# emat_igbt_switch.net
KiCad netlist of a schematic drawn in EAGLE
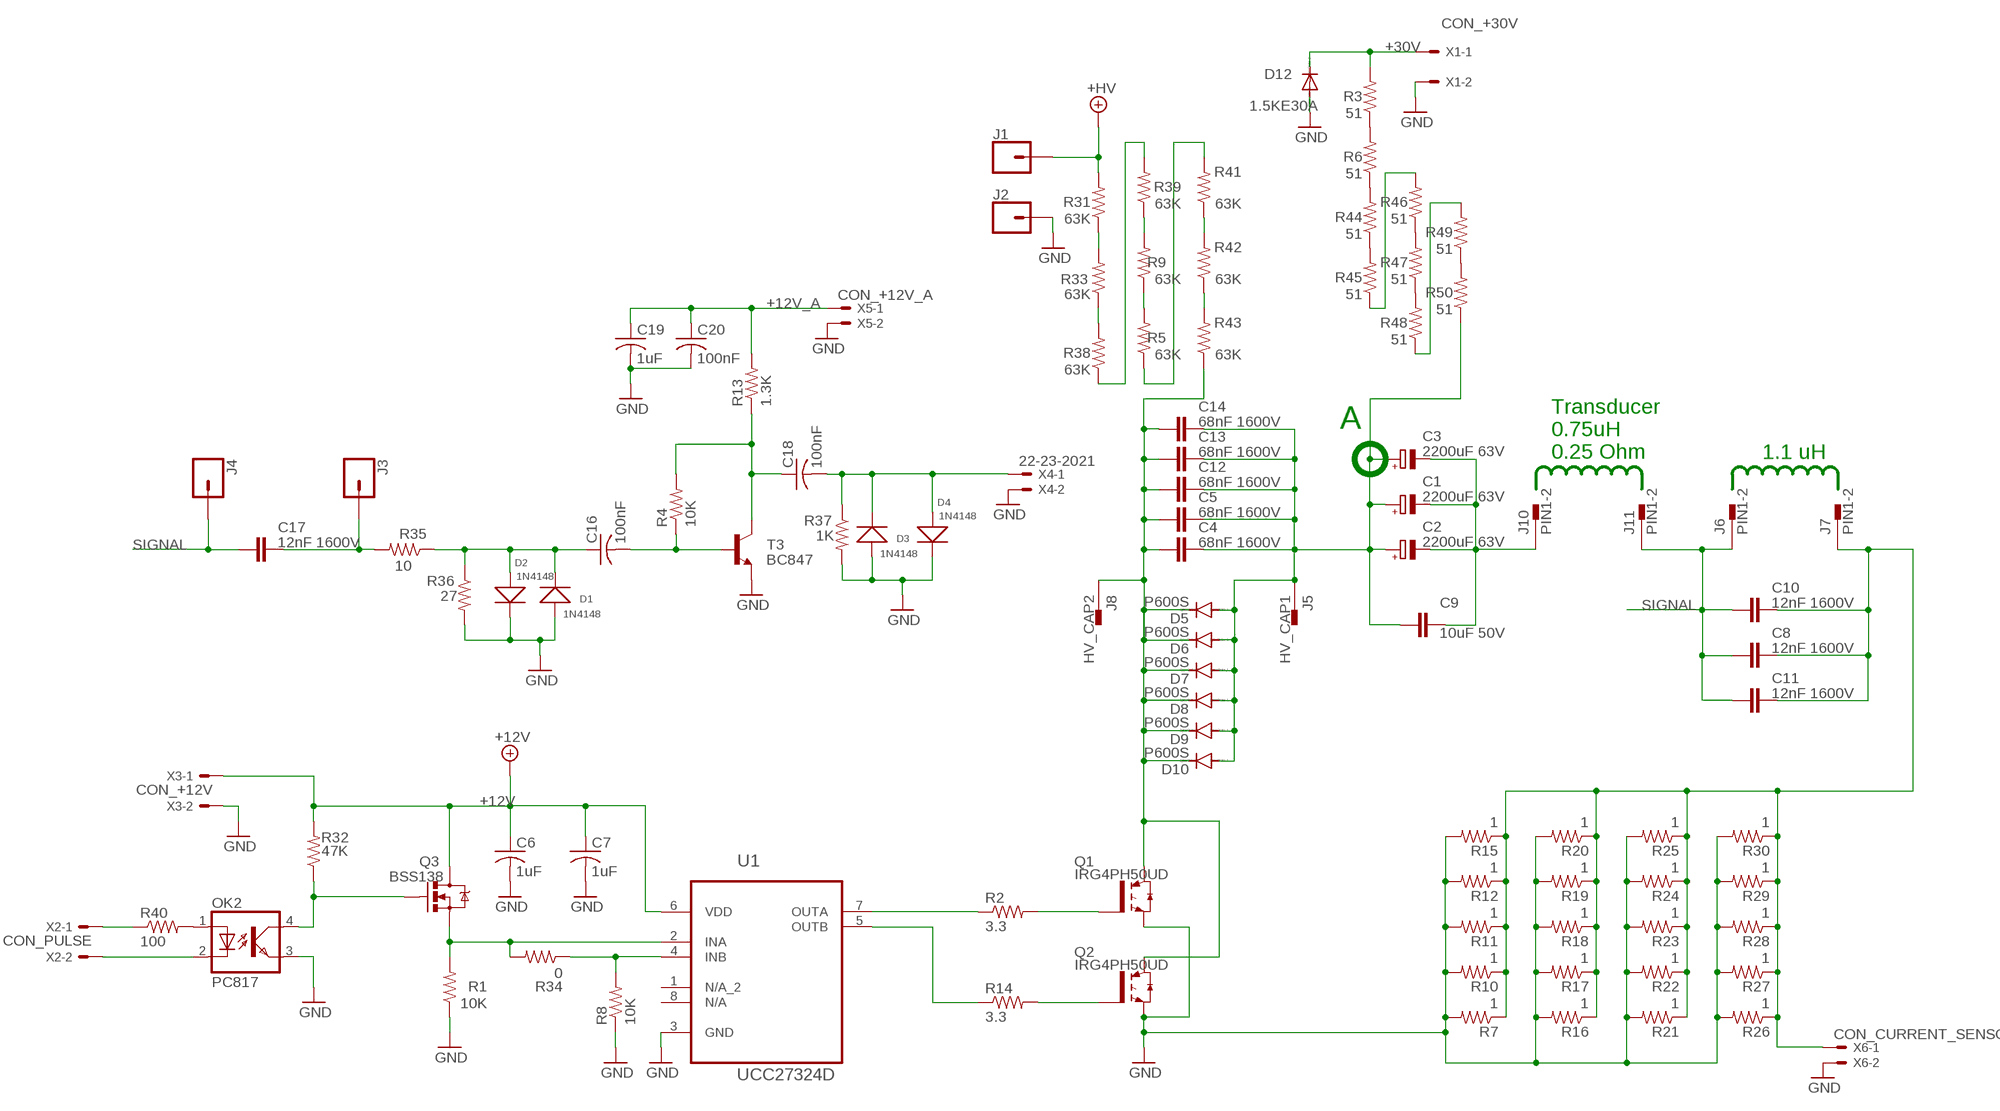
[diagram p0: schematic, sheet 1]

(export (version "E")
  (design (tool "Eeschema 10.0.6"))
  (components
    (comp (ref "C1")
      (value "2200uF 63V")
      (footprint "eagle-import:E7,5-18")
      (libsource (lib "eagle-import") (part "CPOL-EUE7.5-18"))
    )
    (comp (ref "C2")
      (value "2200uF 63V")
      (footprint "eagle-import:E7,5-18")
      (libsource (lib "eagle-import") (part "CPOL-EUE7.5-18"))
    )
    (comp (ref "C3")
      (value "2200uF 63V")
      (footprint "eagle-import:E7,5-18")
      (libsource (lib "eagle-import") (part "CPOL-EUE7.5-18"))
    )
    (comp (ref "C4")
      (value "68nF 1600V")
      (footprint "eagle-import:C37.5B15")
      (libsource (lib "eagle-import") (part "C37/15"))
    )
    (comp (ref "C5")
      (value "68nF 1600V")
      (footprint "eagle-import:C37.5B15")
      (libsource (lib "eagle-import") (part "C37/15"))
    )
    (comp (ref "C6")
      (value "1uF")
      (footprint "eagle-import:C0805")
      (libsource (lib "eagle-import") (part "C-USC0805"))
    )
    (comp (ref "C7")
      (value "1uF")
      (footprint "eagle-import:C0805")
      (libsource (lib "eagle-import") (part "C-USC0805"))
    )
    (comp (ref "C8")
      (value "12nF 1600V")
      (footprint "eagle-import:C22.5B10")
      (libsource (lib "eagle-import") (part "C22/10"))
    )
    (comp (ref "C9")
      (value "10uF 50V")
      (footprint "eagle-import:C2220K")
      (libsource (lib "eagle-import") (part "C-EUC2220K"))
    )
    (comp (ref "C10")
      (value "12nF 1600V")
      (footprint "eagle-import:C22.5B10")
      (libsource (lib "eagle-import") (part "C22/10"))
    )
    (comp (ref "C11")
      (value "12nF 1600V")
      (footprint "eagle-import:C22.5B10")
      (libsource (lib "eagle-import") (part "C22/10"))
    )
    (comp (ref "C12")
      (value "68nF 1600V")
      (footprint "eagle-import:C37.5B15")
      (libsource (lib "eagle-import") (part "C37/15"))
    )
    (comp (ref "C13")
      (value "68nF 1600V")
      (footprint "eagle-import:C37.5B15")
      (libsource (lib "eagle-import") (part "C37/15"))
    )
    (comp (ref "C14")
      (value "68nF 1600V")
      (footprint "eagle-import:C37.5B15")
      (libsource (lib "eagle-import") (part "C37/15"))
    )
    (comp (ref "C16")
      (value "100nF")
      (footprint "eagle-import:C0805")
      (libsource (lib "eagle-import") (part "C-USC0805"))
    )
    (comp (ref "C17")
      (value "12nF 1600V")
      (footprint "eagle-import:C22.5B10")
      (libsource (lib "eagle-import") (part "C22/10"))
    )
    (comp (ref "C18")
      (value "100nF")
      (footprint "eagle-import:C0805")
      (libsource (lib "eagle-import") (part "C-USC0805"))
    )
    (comp (ref "C19")
      (value "1uF")
      (footprint "eagle-import:C0805")
      (libsource (lib "eagle-import") (part "C-USC0805"))
    )
    (comp (ref "C20")
      (value "100nF")
      (footprint "eagle-import:C0805")
      (libsource (lib "eagle-import") (part "C-USC0805"))
    )
    (comp (ref "D1")
      (value "1N4148")
      (footprint "eagle-import:LL-34")
      (libsource (lib "eagle-import") (part "SMD-DIODE-SWITCH-1N4148(LL-34)"))
    )
    (comp (ref "D2")
      (value "1N4148")
      (footprint "eagle-import:LL-34")
      (libsource (lib "eagle-import") (part "SMD-DIODE-SWITCH-1N4148(LL-34)"))
    )
    (comp (ref "D3")
      (value "1N4148")
      (footprint "eagle-import:LL-34")
      (libsource (lib "eagle-import") (part "SMD-DIODE-SWITCH-1N4148(LL-34)"))
    )
    (comp (ref "D4")
      (value "1N4148")
      (footprint "eagle-import:LL-34")
      (libsource (lib "eagle-import") (part "SMD-DIODE-SWITCH-1N4148(LL-34)"))
    )
    (comp (ref "D5")
      (value "P600S")
      (footprint "eagle-import:P6-15")
      (libsource (lib "eagle-import") (part "P600"))
    )
    (comp (ref "D6")
      (value "P600S")
      (footprint "eagle-import:P6-15")
      (libsource (lib "eagle-import") (part "P600"))
    )
    (comp (ref "D7")
      (value "P600S")
      (footprint "eagle-import:P6-15")
      (libsource (lib "eagle-import") (part "P600"))
    )
    (comp (ref "D8")
      (value "P600S")
      (footprint "eagle-import:P6-15")
      (libsource (lib "eagle-import") (part "P600"))
    )
    (comp (ref "D9")
      (value "P600S")
      (footprint "eagle-import:P6-15")
      (libsource (lib "eagle-import") (part "P600"))
    )
    (comp (ref "D10")
      (value "P600S")
      (footprint "eagle-import:P6-15")
      (libsource (lib "eagle-import") (part "P600"))
    )
    (comp (ref "D12")
      (value "1.5KE30A")
      (footprint "eagle-import:SMC")
      (libsource (lib "eagle-import") (part "DIODE-SMC"))
    )
    (comp (ref "J1")
      (value "CONN_01PTH_NO_SILK_KIT")
      (footprint "eagle-import:1X01NS_KIT")
      (libsource (lib "eagle-import") (part "CONN_01PTH_NO_SILK_KIT"))
    )
    (comp (ref "J2")
      (value "CONN_01PTH_NO_SILK_KIT")
      (footprint "eagle-import:1X01NS_KIT")
      (libsource (lib "eagle-import") (part "CONN_01PTH_NO_SILK_KIT"))
    )
    (comp (ref "J3")
      (value "CONN_01PTH_NO_SILK_KIT")
      (footprint "eagle-import:1X01NS_KIT")
      (libsource (lib "eagle-import") (part "CONN_01PTH_NO_SILK_KIT"))
    )
    (comp (ref "J4")
      (value "CONN_01PTH_NO_SILK_KIT")
      (footprint "eagle-import:1X01NS_KIT")
      (libsource (lib "eagle-import") (part "CONN_01PTH_NO_SILK_KIT"))
    )
    (comp (ref "J5")
      (value "HV_CAP1")
      (footprint "eagle-import:62221")
      (fields (field (name "MF") "TYCO ELECTRONICS") (field (name "MPN") "62221-1"))
      (libsource (lib "eagle-import") (part "PIN1-2"))
    )
    (comp (ref "J6")
      (value "PIN1-2")
      (footprint "eagle-import:62221")
      (fields (field (name "MF") "TYCO ELECTRONICS") (field (name "MPN") "62221-1"))
      (libsource (lib "eagle-import") (part "PIN1-2"))
    )
    (comp (ref "J7")
      (value "PIN1-2")
      (footprint "eagle-import:62221")
      (fields (field (name "MF") "TYCO ELECTRONICS") (field (name "MPN") "62221-1"))
      (libsource (lib "eagle-import") (part "PIN1-2"))
    )
    (comp (ref "J8")
      (value "HV_CAP2")
      (footprint "eagle-import:62221")
      (fields (field (name "MF") "TYCO ELECTRONICS") (field (name "MPN") "62221-1"))
      (libsource (lib "eagle-import") (part "PIN1-2"))
    )
    (comp (ref "J10")
      (value "PIN1-2")
      (footprint "eagle-import:62221")
      (fields (field (name "MF") "TYCO ELECTRONICS") (field (name "MPN") "62221-1"))
      (libsource (lib "eagle-import") (part "PIN1-2"))
    )
    (comp (ref "J11")
      (value "PIN1-2")
      (footprint "eagle-import:62221")
      (fields (field (name "MF") "TYCO ELECTRONICS") (field (name "MPN") "62221-1"))
      (libsource (lib "eagle-import") (part "PIN1-2"))
    )
    (comp (ref "OK2")
      (value "PC817")
      (footprint "eagle-import:DIL04")
      (fields (field (name "MPN") "PC817X4J000F"))
      (libsource (lib "eagle-import") (part "PC817"))
    )
    (comp (ref "Q1")
      (value "IRG4PH50UD")
      (footprint "eagle-import:TO247BV")
      (libsource (lib "eagle-import") (part "IGBT_TO247"))
    )
    (comp (ref "Q2")
      (value "IRG4PH50UD")
      (footprint "eagle-import:TO247BV")
      (libsource (lib "eagle-import") (part "IGBT_TO247"))
    )
    (comp (ref "Q3")
      (value "BSS138")
      (footprint "eagle-import:SOT23-3")
      (libsource (lib "eagle-import") (part "MOSFET-NCHANNELBSS138"))
    )
    (comp (ref "R1")
      (value "10K")
      (footprint "eagle-import:R1206")
      (libsource (lib "eagle-import") (part "R-US_R1206"))
    )
    (comp (ref "R2")
      (value "3.3")
      (footprint "eagle-import:R1206")
      (libsource (lib "eagle-import") (part "R-US_R1206"))
    )
    (comp (ref "R3")
      (value "51")
      (footprint "eagle-import:R1206")
      (libsource (lib "eagle-import") (part "R-US_R1206"))
    )
    (comp (ref "R4")
      (value "10K")
      (footprint "eagle-import:R1206")
      (libsource (lib "eagle-import") (part "R-US_R1206"))
    )
    (comp (ref "R5")
      (value "63K")
      (footprint "eagle-import:R1206")
      (libsource (lib "eagle-import") (part "R-US_R1206"))
    )
    (comp (ref "R6")
      (value "51")
      (footprint "eagle-import:R1206")
      (libsource (lib "eagle-import") (part "R-US_R1206"))
    )
    (comp (ref "R7")
      (value "1")
      (footprint "eagle-import:R1206")
      (libsource (lib "eagle-import") (part "R-US_R1206"))
    )
    (comp (ref "R8")
      (value "10K")
      (footprint "eagle-import:R1206")
      (libsource (lib "eagle-import") (part "R-US_R1206"))
    )
    (comp (ref "R9")
      (value "63K")
      (footprint "eagle-import:R1206")
      (libsource (lib "eagle-import") (part "R-US_R1206"))
    )
    (comp (ref "R10")
      (value "1")
      (footprint "eagle-import:R1206")
      (libsource (lib "eagle-import") (part "R-US_R1206"))
    )
    (comp (ref "R11")
      (value "1")
      (footprint "eagle-import:R1206")
      (libsource (lib "eagle-import") (part "R-US_R1206"))
    )
    (comp (ref "R12")
      (value "1")
      (footprint "eagle-import:R1206")
      (libsource (lib "eagle-import") (part "R-US_R1206"))
    )
    (comp (ref "R13")
      (value "1.3K")
      (footprint "eagle-import:R1206")
      (libsource (lib "eagle-import") (part "R-US_R1206"))
    )
    (comp (ref "R14")
      (value "3.3")
      (footprint "eagle-import:R1206")
      (libsource (lib "eagle-import") (part "R-US_R1206"))
    )
    (comp (ref "R15")
      (value "1")
      (footprint "eagle-import:R1206")
      (libsource (lib "eagle-import") (part "R-US_R1206"))
    )
    (comp (ref "R16")
      (value "1")
      (footprint "eagle-import:R1206")
      (libsource (lib "eagle-import") (part "R-US_R1206"))
    )
    (comp (ref "R17")
      (value "1")
      (footprint "eagle-import:R1206")
      (libsource (lib "eagle-import") (part "R-US_R1206"))
    )
    (comp (ref "R18")
      (value "1")
      (footprint "eagle-import:R1206")
      (libsource (lib "eagle-import") (part "R-US_R1206"))
    )
    (comp (ref "R19")
      (value "1")
      (footprint "eagle-import:R1206")
      (libsource (lib "eagle-import") (part "R-US_R1206"))
    )
    (comp (ref "R20")
      (value "1")
      (footprint "eagle-import:R1206")
      (libsource (lib "eagle-import") (part "R-US_R1206"))
    )
    (comp (ref "R21")
      (value "1")
      (footprint "eagle-import:R1206")
      (libsource (lib "eagle-import") (part "R-US_R1206"))
    )
    (comp (ref "R22")
      (value "1")
      (footprint "eagle-import:R1206")
      (libsource (lib "eagle-import") (part "R-US_R1206"))
    )
    (comp (ref "R23")
      (value "1")
      (footprint "eagle-import:R1206")
      (libsource (lib "eagle-import") (part "R-US_R1206"))
    )
    (comp (ref "R24")
      (value "1")
      (footprint "eagle-import:R1206")
      (libsource (lib "eagle-import") (part "R-US_R1206"))
    )
    (comp (ref "R25")
      (value "1")
      (footprint "eagle-import:R1206")
      (libsource (lib "eagle-import") (part "R-US_R1206"))
    )
    (comp (ref "R26")
      (value "1")
      (footprint "eagle-import:R1206")
      (libsource (lib "eagle-import") (part "R-US_R1206"))
    )
    (comp (ref "R27")
      (value "1")
      (footprint "eagle-import:R1206")
      (libsource (lib "eagle-import") (part "R-US_R1206"))
    )
    (comp (ref "R28")
      (value "1")
      (footprint "eagle-import:R1206")
      (libsource (lib "eagle-import") (part "R-US_R1206"))
    )
    (comp (ref "R29")
      (value "1")
      (footprint "eagle-import:R1206")
      (libsource (lib "eagle-import") (part "R-US_R1206"))
    )
    (comp (ref "R30")
      (value "1")
      (footprint "eagle-import:R1206")
      (libsource (lib "eagle-import") (part "R-US_R1206"))
    )
    (comp (ref "R31")
      (value "63K")
      (footprint "eagle-import:R1206")
      (libsource (lib "eagle-import") (part "R-US_R1206"))
    )
    (comp (ref "R32")
      (value "47K")
      (footprint "eagle-import:R1206")
      (libsource (lib "eagle-import") (part "R-US_R1206"))
    )
    (comp (ref "R33")
      (value "63K")
      (footprint "eagle-import:R1206")
      (libsource (lib "eagle-import") (part "R-US_R1206"))
    )
    (comp (ref "R34")
      (value "0")
      (footprint "eagle-import:R1206")
      (libsource (lib "eagle-import") (part "R-US_R1206"))
    )
    (comp (ref "R35")
      (value "10")
      (footprint "eagle-import:R1206")
      (libsource (lib "eagle-import") (part "R-US_R1206"))
    )
    (comp (ref "R36")
      (value "27")
      (footprint "eagle-import:R1206")
      (libsource (lib "eagle-import") (part "R-US_R1206"))
    )
    (comp (ref "R37")
      (value "1K")
      (footprint "eagle-import:R1206")
      (libsource (lib "eagle-import") (part "R-US_R1206"))
    )
    (comp (ref "R38")
      (value "63K")
      (footprint "eagle-import:R1206")
      (libsource (lib "eagle-import") (part "R-US_R1206"))
    )
    (comp (ref "R39")
      (value "63K")
      (footprint "eagle-import:R1206")
      (libsource (lib "eagle-import") (part "R-US_R1206"))
    )
    (comp (ref "R40")
      (value "100")
      (footprint "eagle-import:R1206")
      (libsource (lib "eagle-import") (part "resistor_R-US_R1206"))
    )
    (comp (ref "R41")
      (value "63K")
      (footprint "eagle-import:R1206")
      (libsource (lib "eagle-import") (part "R-US_R1206"))
    )
    (comp (ref "R42")
      (value "63K")
      (footprint "eagle-import:R1206")
      (libsource (lib "eagle-import") (part "R-US_R1206"))
    )
    (comp (ref "R43")
      (value "63K")
      (footprint "eagle-import:R1206")
      (libsource (lib "eagle-import") (part "R-US_R1206"))
    )
    (comp (ref "R44")
      (value "51")
      (footprint "eagle-import:R1206")
      (libsource (lib "eagle-import") (part "R-US_R1206"))
    )
    (comp (ref "R45")
      (value "51")
      (footprint "eagle-import:R1206")
      (libsource (lib "eagle-import") (part "R-US_R1206"))
    )
    (comp (ref "R46")
      (value "51")
      (footprint "eagle-import:R1206")
      (libsource (lib "eagle-import") (part "R-US_R1206"))
    )
    (comp (ref "R47")
      (value "51")
      (footprint "eagle-import:R1206")
      (libsource (lib "eagle-import") (part "R-US_R1206"))
    )
    (comp (ref "R48")
      (value "51")
      (footprint "eagle-import:R1206")
      (libsource (lib "eagle-import") (part "R-US_R1206"))
    )
    (comp (ref "R49")
      (value "51")
      (footprint "eagle-import:R1206")
      (libsource (lib "eagle-import") (part "R-US_R1206"))
    )
    (comp (ref "R50")
      (value "51")
      (footprint "eagle-import:R1206")
      (libsource (lib "eagle-import") (part "R-US_R1206"))
    )
    (comp (ref "T3")
      (value "BC847")
      (footprint "eagle-import:SOT23-BEC")
      (libsource (lib "eagle-import") (part "-NPN-SOT23-BEC"))
    )
    (comp (ref "U1")
      (value "UCC27324D")
      (footprint "eagle-import:SOIC127P600X175-8N")
      (libsource (lib "eagle-import") (part "UCC27324D"))
    )
    (comp (ref "X1")
      (value "CON_+30V")
      (footprint "eagle-import:22-23-2021")
      (fields (field (name "MF") "MOLEX") (field (name "MPN") "22-23-2021"))
      (libsource (lib "eagle-import") (part "22-23-2021"))
    )
    (comp (ref "X2")
      (value "CON_PULSE")
      (footprint "eagle-import:22-23-2021")
      (fields (field (name "MF") "MOLEX") (field (name "MPN") "22-23-2021"))
      (libsource (lib "eagle-import") (part "22-23-2021"))
    )
    (comp (ref "X3")
      (value "CON_+12V")
      (footprint "eagle-import:22-23-2021")
      (fields (field (name "MF") "MOLEX") (field (name "MPN") "22-23-2021"))
      (libsource (lib "eagle-import") (part "22-23-2021"))
    )
    (comp (ref "X4")
      (value "22-23-2021")
      (footprint "eagle-import:22-23-2021")
      (fields (field (name "MF") "MOLEX"))
      (libsource (lib "eagle-import") (part "22-23-2021"))
    )
    (comp (ref "X5")
      (value "CON_+12V_A")
      (footprint "eagle-import:22-23-2021")
      (fields (field (name "MF") "MOLEX") (field (name "MPN") "22-23-2021"))
      (libsource (lib "eagle-import") (part "22-23-2021"))
    )
    (comp (ref "X6")
      (value "CON_CURRENT_SENSOR")
      (footprint "eagle-import:22-23-2021")
      (fields (field (name "MF") "MOLEX") (field (name "MPN") "22-23-2021"))
      (libsource (lib "eagle-import") (part "22-23-2021"))
    )
  )
  (nets
    (net (code "1") (name "+12V") (class "Default")
      (node (ref "C6") (pin "1") (pinfunction "1_1") (pintype "passive"))
      (node (ref "C7") (pin "1") (pinfunction "1_1") (pintype "passive"))
      (node (ref "Q3") (pin "3") (pinfunction "D_3") (pintype "passive"))
      (node (ref "R32") (pin "2") (pinfunction "2_2") (pintype "passive"))
      (node (ref "U1") (pin "6") (pinfunction "VDD_6") (pintype "power_in"))
      (node (ref "X3") (pin "1") (pinfunction "S_1") (pintype "passive"))
    )
    (net (code "2") (name "+HV") (class "Default")
      (node (ref "J1") (pin "1") (pinfunction "1_1") (pintype "passive"))
      (node (ref "R31") (pin "2") (pinfunction "2_2") (pintype "passive"))
    )
    (net (code "3") (name "/+12V_A") (class "Default")
      (node (ref "C19") (pin "1") (pinfunction "1_1") (pintype "passive"))
      (node (ref "C20") (pin "1") (pinfunction "1_1") (pintype "passive"))
      (node (ref "R13") (pin "2") (pinfunction "2_2") (pintype "passive"))
      (node (ref "X5") (pin "1") (pinfunction "S_1") (pintype "passive"))
    )
    (net (code "4") (name "/+30V") (class "Default")
      (node (ref "D12") (pin "C") (pinfunction "C_C") (pintype "passive"))
      (node (ref "R3") (pin "2") (pinfunction "2_2") (pintype "passive"))
      (node (ref "X1") (pin "1") (pinfunction "S_1") (pintype "passive"))
    )
    (net (code "5") (name "/SIGNAL") (class "Default")
      (node (ref "C10") (pin "1") (pinfunction "1_1") (pintype "passive"))
      (node (ref "C11") (pin "1") (pinfunction "1_1") (pintype "passive"))
      (node (ref "C17") (pin "1") (pinfunction "1_1") (pintype "passive"))
      (node (ref "C8") (pin "1") (pinfunction "1_1") (pintype "passive"))
      (node (ref "J11") (pin "1") (pinfunction "1_1") (pintype "passive"))
      (node (ref "J4") (pin "1") (pinfunction "1_1") (pintype "passive"))
      (node (ref "J6") (pin "1") (pinfunction "1_1") (pintype "passive"))
    )
    (net (code "6") (name "GND") (class "Default")
      (node (ref "C19") (pin "2") (pinfunction "2_2") (pintype "passive"))
      (node (ref "C20") (pin "2") (pinfunction "2_2") (pintype "passive"))
      (node (ref "C6") (pin "2") (pinfunction "2_2") (pintype "passive"))
      (node (ref "C7") (pin "2") (pinfunction "2_2") (pintype "passive"))
      (node (ref "D1") (pin "A") (pinfunction "+_A") (pintype "passive"))
      (node (ref "D12") (pin "A") (pinfunction "A_A") (pintype "passive"))
      (node (ref "D2") (pin "C") (pinfunction "-_C") (pintype "passive"))
      (node (ref "D3") (pin "A") (pinfunction "+_A") (pintype "passive"))
      (node (ref "D4") (pin "C") (pinfunction "-_C") (pintype "passive"))
      (node (ref "J2") (pin "1") (pinfunction "1_1") (pintype "passive"))
      (node (ref "OK2") (pin "3") (pinfunction "EMIT_3") (pintype "passive"))
      (node (ref "Q1") (pin "S") (pinfunction "E_S") (pintype "passive"))
      (node (ref "Q2") (pin "S") (pinfunction "E_S") (pintype "passive"))
      (node (ref "R1") (pin "1") (pinfunction "1_1") (pintype "passive"))
      (node (ref "R10") (pin "2") (pinfunction "2_2") (pintype "passive"))
      (node (ref "R11") (pin "2") (pinfunction "2_2") (pintype "passive"))
      (node (ref "R12") (pin "2") (pinfunction "2_2") (pintype "passive"))
      (node (ref "R15") (pin "2") (pinfunction "2_2") (pintype "passive"))
      (node (ref "R16") (pin "2") (pinfunction "2_2") (pintype "passive"))
      (node (ref "R17") (pin "2") (pinfunction "2_2") (pintype "passive"))
      (node (ref "R18") (pin "2") (pinfunction "2_2") (pintype "passive"))
      (node (ref "R19") (pin "2") (pinfunction "2_2") (pintype "passive"))
      (node (ref "R20") (pin "2") (pinfunction "2_2") (pintype "passive"))
      (node (ref "R21") (pin "2") (pinfunction "2_2") (pintype "passive"))
      (node (ref "R22") (pin "2") (pinfunction "2_2") (pintype "passive"))
      (node (ref "R23") (pin "2") (pinfunction "2_2") (pintype "passive"))
      (node (ref "R24") (pin "2") (pinfunction "2_2") (pintype "passive"))
      (node (ref "R25") (pin "2") (pinfunction "2_2") (pintype "passive"))
      (node (ref "R26") (pin "2") (pinfunction "2_2") (pintype "passive"))
      (node (ref "R27") (pin "2") (pinfunction "2_2") (pintype "passive"))
      (node (ref "R28") (pin "2") (pinfunction "2_2") (pintype "passive"))
      (node (ref "R29") (pin "2") (pinfunction "2_2") (pintype "passive"))
      (node (ref "R30") (pin "2") (pinfunction "2_2") (pintype "passive"))
      (node (ref "R36") (pin "2") (pinfunction "2_2") (pintype "passive"))
      (node (ref "R37") (pin "2") (pinfunction "2_2") (pintype "passive"))
      (node (ref "R7") (pin "2") (pinfunction "2_2") (pintype "passive"))
      (node (ref "R8") (pin "1") (pinfunction "1_1") (pintype "passive"))
      (node (ref "T3") (pin "E") (pinfunction "E_E") (pintype "passive"))
      (node (ref "U1") (pin "3") (pinfunction "GND_3") (pintype "passive"))
      (node (ref "X1") (pin "2") (pinfunction "S_2") (pintype "passive"))
      (node (ref "X3") (pin "2") (pinfunction "S_2") (pintype "passive"))
      (node (ref "X4") (pin "2") (pinfunction "S_2") (pintype "passive"))
      (node (ref "X5") (pin "2") (pinfunction "S_2") (pintype "passive"))
      (node (ref "X6") (pin "2") (pinfunction "S_2") (pintype "passive"))
    )
    (net (code "7") (name "Net-(C1-Pad+)") (class "Default")
      (node (ref "C1") (pin "+") (pinfunction "+_+") (pintype "passive"))
      (node (ref "C12") (pin "2") (pinfunction "2_2") (pintype "passive"))
      (node (ref "C13") (pin "2") (pinfunction "2_2") (pintype "passive"))
      (node (ref "C14") (pin "2") (pinfunction "2_2") (pintype "passive"))
      (node (ref "C2") (pin "+") (pinfunction "+_+") (pintype "passive"))
      (node (ref "C3") (pin "+") (pinfunction "+_+") (pintype "passive"))
      (node (ref "C4") (pin "2") (pinfunction "2_2") (pintype "passive"))
      (node (ref "C5") (pin "2") (pinfunction "2_2") (pintype "passive"))
      (node (ref "C9") (pin "1") (pinfunction "1_1") (pintype "passive"))
      (node (ref "D10") (pin "A") (pinfunction "A_A") (pintype "passive"))
      (node (ref "D5") (pin "A") (pinfunction "A_A") (pintype "passive"))
      (node (ref "D6") (pin "A") (pinfunction "A_A") (pintype "passive"))
      (node (ref "D7") (pin "A") (pinfunction "A_A") (pintype "passive"))
      (node (ref "D8") (pin "A") (pinfunction "A_A") (pintype "passive"))
      (node (ref "D9") (pin "A") (pinfunction "A_A") (pintype "passive"))
      (node (ref "J5") (pin "1") (pinfunction "1_1") (pintype "passive"))
      (node (ref "R50") (pin "1") (pinfunction "1_1") (pintype "passive"))
    )
    (net (code "8") (name "Net-(C1-Pad-)") (class "Default")
      (node (ref "C1") (pin "-") (pinfunction "-_-") (pintype "passive"))
      (node (ref "C2") (pin "-") (pinfunction "-_-") (pintype "passive"))
      (node (ref "C3") (pin "-") (pinfunction "-_-") (pintype "passive"))
      (node (ref "C9") (pin "2") (pinfunction "2_2") (pintype "passive"))
      (node (ref "J10") (pin "1") (pinfunction "1_1") (pintype "passive"))
    )
    (net (code "9") (name "Net-(C16-Pad2)") (class "Default")
      (node (ref "C16") (pin "2") (pinfunction "2_2") (pintype "passive"))
      (node (ref "R4") (pin "1") (pinfunction "1_1") (pintype "passive"))
      (node (ref "T3") (pin "B") (pinfunction "B_B") (pintype "passive"))
    )
    (net (code "10") (name "Net-(C17-Pad2)") (class "Default")
      (node (ref "C17") (pin "2") (pinfunction "2_2") (pintype "passive"))
      (node (ref "J3") (pin "1") (pinfunction "1_1") (pintype "passive"))
      (node (ref "R35") (pin "2") (pinfunction "2_2") (pintype "passive"))
    )
    (net (code "11") (name "Net-(C18-Pad1)") (class "Default")
      (node (ref "C18") (pin "1") (pinfunction "1_1") (pintype "passive"))
      (node (ref "R13") (pin "1") (pinfunction "1_1") (pintype "passive"))
      (node (ref "R4") (pin "2") (pinfunction "2_2") (pintype "passive"))
      (node (ref "T3") (pin "C") (pinfunction "C_C") (pintype "passive"))
    )
    (net (code "12") (name "Net-(D1--)") (class "Default")
      (node (ref "C16") (pin "1") (pinfunction "1_1") (pintype "passive"))
      (node (ref "D1") (pin "C") (pinfunction "-_C") (pintype "passive"))
      (node (ref "D2") (pin "A") (pinfunction "+_A") (pintype "passive"))
      (node (ref "R35") (pin "1") (pinfunction "1_1") (pintype "passive"))
      (node (ref "R36") (pin "1") (pinfunction "1_1") (pintype "passive"))
    )
    (net (code "13") (name "Net-(D3--)") (class "Default")
      (node (ref "C18") (pin "2") (pinfunction "2_2") (pintype "passive"))
      (node (ref "D3") (pin "C") (pinfunction "-_C") (pintype "passive"))
      (node (ref "D4") (pin "A") (pinfunction "+_A") (pintype "passive"))
      (node (ref "R37") (pin "1") (pinfunction "1_1") (pintype "passive"))
      (node (ref "X4") (pin "1") (pinfunction "S_1") (pintype "passive"))
    )
    (net (code "14") (name "Net-(OK2-A)") (class "Default")
      (node (ref "OK2") (pin "1") (pinfunction "A_1") (pintype "passive"))
      (node (ref "R40") (pin "2") (pinfunction "2_2") (pintype "passive"))
    )
    (net (code "15") (name "Net-(OK2-C)") (class "Default")
      (node (ref "OK2") (pin "2") (pinfunction "C_2") (pintype "passive"))
      (node (ref "X2") (pin "2") (pinfunction "S_2") (pintype "passive"))
    )
    (net (code "16") (name "Net-(OK2-COL)") (class "Default")
      (node (ref "OK2") (pin "4") (pinfunction "COL_4") (pintype "passive"))
      (node (ref "Q3") (pin "1") (pinfunction "G_1") (pintype "passive"))
      (node (ref "R32") (pin "1") (pinfunction "1_1") (pintype "passive"))
    )
    (net (code "17") (name "Net-(Q1-C)") (class "Default")
      (node (ref "C12") (pin "1") (pinfunction "1_1") (pintype "passive"))
      (node (ref "C13") (pin "1") (pinfunction "1_1") (pintype "passive"))
      (node (ref "C14") (pin "1") (pinfunction "1_1") (pintype "passive"))
      (node (ref "C4") (pin "1") (pinfunction "1_1") (pintype "passive"))
      (node (ref "C5") (pin "1") (pinfunction "1_1") (pintype "passive"))
      (node (ref "D10") (pin "C") (pinfunction "C_C") (pintype "passive"))
      (node (ref "D5") (pin "C") (pinfunction "C_C") (pintype "passive"))
      (node (ref "D6") (pin "C") (pinfunction "C_C") (pintype "passive"))
      (node (ref "D7") (pin "C") (pinfunction "C_C") (pintype "passive"))
      (node (ref "D8") (pin "C") (pinfunction "C_C") (pintype "passive"))
      (node (ref "D9") (pin "C") (pinfunction "C_C") (pintype "passive"))
      (node (ref "J8") (pin "1") (pinfunction "1_1") (pintype "passive"))
      (node (ref "Q1") (pin "D") (pinfunction "C_D") (pintype "passive"))
      (node (ref "Q2") (pin "D") (pinfunction "C_D") (pintype "passive"))
      (node (ref "R43") (pin "1") (pinfunction "1_1") (pintype "passive"))
    )
    (net (code "18") (name "Net-(Q1-PadG)") (class "Default")
      (node (ref "Q1") (pin "G") (pinfunction "G_G") (pintype "passive"))
      (node (ref "R2") (pin "2") (pinfunction "2_2") (pintype "passive"))
    )
    (net (code "19") (name "Net-(Q2-PadG)") (class "Default")
      (node (ref "Q2") (pin "G") (pinfunction "G_G") (pintype "passive"))
      (node (ref "R14") (pin "2") (pinfunction "2_2") (pintype "passive"))
    )
    (net (code "20") (name "Net-(Q3-S)") (class "Default")
      (node (ref "Q3") (pin "2") (pinfunction "S_2") (pintype "passive"))
      (node (ref "R1") (pin "2") (pinfunction "2_2") (pintype "passive"))
      (node (ref "R34") (pin "2") (pinfunction "2_2") (pintype "passive"))
      (node (ref "U1") (pin "2") (pinfunction "INA_2") (pintype "input"))
    )
    (net (code "21") (name "Net-(R3-Pad1)") (class "Default")
      (node (ref "R3") (pin "1") (pinfunction "1_1") (pintype "passive"))
      (node (ref "R6") (pin "2") (pinfunction "2_2") (pintype "passive"))
    )
    (net (code "22") (name "Net-(R5-Pad2)") (class "Default")
      (node (ref "R5") (pin "2") (pinfunction "2_2") (pintype "passive"))
      (node (ref "R9") (pin "1") (pinfunction "1_1") (pintype "passive"))
    )
    (net (code "23") (name "Net-(R31-Pad1)") (class "Default")
      (node (ref "R31") (pin "1") (pinfunction "1_1") (pintype "passive"))
      (node (ref "R33") (pin "2") (pinfunction "2_2") (pintype "passive"))
    )
    (net (code "24") (name "Net-(R33-Pad1)") (class "Default")
      (node (ref "R33") (pin "1") (pinfunction "1_1") (pintype "passive"))
      (node (ref "R38") (pin "2") (pinfunction "2_2") (pintype "passive"))
    )
    (net (code "25") (name "Net-(R38-Pad1)") (class "Default")
      (node (ref "R38") (pin "1") (pinfunction "1_1") (pintype "passive"))
      (node (ref "R39") (pin "2") (pinfunction "2_2") (pintype "passive"))
    )
    (net (code "26") (name "Net-(R39-Pad1)") (class "Default")
      (node (ref "R39") (pin "1") (pinfunction "1_1") (pintype "passive"))
      (node (ref "R9") (pin "2") (pinfunction "2_2") (pintype "passive"))
    )
    (net (code "27") (name "Net-(R41-Pad1)") (class "Default")
      (node (ref "R41") (pin "1") (pinfunction "1_1") (pintype "passive"))
      (node (ref "R42") (pin "2") (pinfunction "2_2") (pintype "passive"))
    )
    (net (code "28") (name "Net-(R41-Pad2)") (class "Default")
      (node (ref "R41") (pin "2") (pinfunction "2_2") (pintype "passive"))
      (node (ref "R5") (pin "1") (pinfunction "1_1") (pintype "passive"))
    )
    (net (code "29") (name "Net-(R42-Pad1)") (class "Default")
      (node (ref "R42") (pin "1") (pinfunction "1_1") (pintype "passive"))
      (node (ref "R43") (pin "2") (pinfunction "2_2") (pintype "passive"))
    )
    (net (code "30") (name "Net-(R44-Pad1)") (class "Default")
      (node (ref "R44") (pin "1") (pinfunction "1_1") (pintype "passive"))
      (node (ref "R45") (pin "2") (pinfunction "2_2") (pintype "passive"))
    )
    (net (code "31") (name "Net-(R44-Pad2)") (class "Default")
      (node (ref "R44") (pin "2") (pinfunction "2_2") (pintype "passive"))
      (node (ref "R6") (pin "1") (pinfunction "1_1") (pintype "passive"))
    )
    (net (code "32") (name "Net-(R45-Pad1)") (class "Default")
      (node (ref "R45") (pin "1") (pinfunction "1_1") (pintype "passive"))
      (node (ref "R46") (pin "2") (pinfunction "2_2") (pintype "passive"))
    )
    (net (code "33") (name "Net-(R46-Pad1)") (class "Default")
      (node (ref "R46") (pin "1") (pinfunction "1_1") (pintype "passive"))
      (node (ref "R47") (pin "2") (pinfunction "2_2") (pintype "passive"))
    )
    (net (code "34") (name "Net-(R47-Pad1)") (class "Default")
      (node (ref "R47") (pin "1") (pinfunction "1_1") (pintype "passive"))
      (node (ref "R48") (pin "2") (pinfunction "2_2") (pintype "passive"))
    )
    (net (code "35") (name "Net-(R48-Pad1)") (class "Default")
      (node (ref "R48") (pin "1") (pinfunction "1_1") (pintype "passive"))
      (node (ref "R49") (pin "2") (pinfunction "2_2") (pintype "passive"))
    )
    (net (code "36") (name "Net-(R49-Pad1)") (class "Default")
      (node (ref "R49") (pin "1") (pinfunction "1_1") (pintype "passive"))
      (node (ref "R50") (pin "2") (pinfunction "2_2") (pintype "passive"))
    )
    (net (code "37") (name "Net-(U1-INB)") (class "Default")
      (node (ref "R34") (pin "1") (pinfunction "1_1") (pintype "passive"))
      (node (ref "R8") (pin "2") (pinfunction "2_2") (pintype "passive"))
      (node (ref "U1") (pin "4") (pinfunction "INB_4") (pintype "input"))
    )
    (net (code "38") (name "Net-(U1-OUTA)") (class "Default")
      (node (ref "R2") (pin "1") (pinfunction "1_1") (pintype "passive"))
      (node (ref "U1") (pin "7") (pinfunction "OUTA_7") (pintype "output"))
    )
    (net (code "39") (name "Net-(U1-OUTB)") (class "Default")
      (node (ref "R14") (pin "1") (pinfunction "1_1") (pintype "passive"))
      (node (ref "U1") (pin "5") (pinfunction "OUTB_5") (pintype "output"))
    )
    (net (code "40") (name "Net-(X2A-S)") (class "Default")
      (node (ref "R40") (pin "1") (pinfunction "1_1") (pintype "passive"))
      (node (ref "X2") (pin "1") (pinfunction "S_1") (pintype "passive"))
    )
    (net (code "41") (name "Net-(X6A-S)") (class "Default")
      (node (ref "C10") (pin "2") (pinfunction "2_2") (pintype "passive"))
      (node (ref "C11") (pin "2") (pinfunction "2_2") (pintype "passive"))
      (node (ref "C8") (pin "2") (pinfunction "2_2") (pintype "passive"))
      (node (ref "J7") (pin "1") (pinfunction "1_1") (pintype "passive"))
      (node (ref "R10") (pin "1") (pinfunction "1_1") (pintype "passive"))
      (node (ref "R11") (pin "1") (pinfunction "1_1") (pintype "passive"))
      (node (ref "R12") (pin "1") (pinfunction "1_1") (pintype "passive"))
      (node (ref "R15") (pin "1") (pinfunction "1_1") (pintype "passive"))
      (node (ref "R16") (pin "1") (pinfunction "1_1") (pintype "passive"))
      (node (ref "R17") (pin "1") (pinfunction "1_1") (pintype "passive"))
      (node (ref "R18") (pin "1") (pinfunction "1_1") (pintype "passive"))
      (node (ref "R19") (pin "1") (pinfunction "1_1") (pintype "passive"))
      (node (ref "R20") (pin "1") (pinfunction "1_1") (pintype "passive"))
      (node (ref "R21") (pin "1") (pinfunction "1_1") (pintype "passive"))
      (node (ref "R22") (pin "1") (pinfunction "1_1") (pintype "passive"))
      (node (ref "R23") (pin "1") (pinfunction "1_1") (pintype "passive"))
      (node (ref "R24") (pin "1") (pinfunction "1_1") (pintype "passive"))
      (node (ref "R25") (pin "1") (pinfunction "1_1") (pintype "passive"))
      (node (ref "R26") (pin "1") (pinfunction "1_1") (pintype "passive"))
      (node (ref "R27") (pin "1") (pinfunction "1_1") (pintype "passive"))
      (node (ref "R28") (pin "1") (pinfunction "1_1") (pintype "passive"))
      (node (ref "R29") (pin "1") (pinfunction "1_1") (pintype "passive"))
      (node (ref "R30") (pin "1") (pinfunction "1_1") (pintype "passive"))
      (node (ref "R7") (pin "1") (pinfunction "1_1") (pintype "passive"))
      (node (ref "X6") (pin "1") (pinfunction "S_1") (pintype "passive"))
    )
    (net (code "42") (name "unconnected-(U1-N{slash}A-Pad8)") (class "Default")
      (node (ref "U1") (pin "8") (pinfunction "N/A_8") (pintype "no_connect"))
    )
    (net (code "43") (name "unconnected-(U1-N{slash}A_2-Pad1)") (class "Default")
      (node (ref "U1") (pin "1") (pinfunction "N/A_2_1") (pintype "no_connect"))
    )
  )
)
